# groovegrid_v2.net
KiCad netlist of a schematic drawn in EAGLE
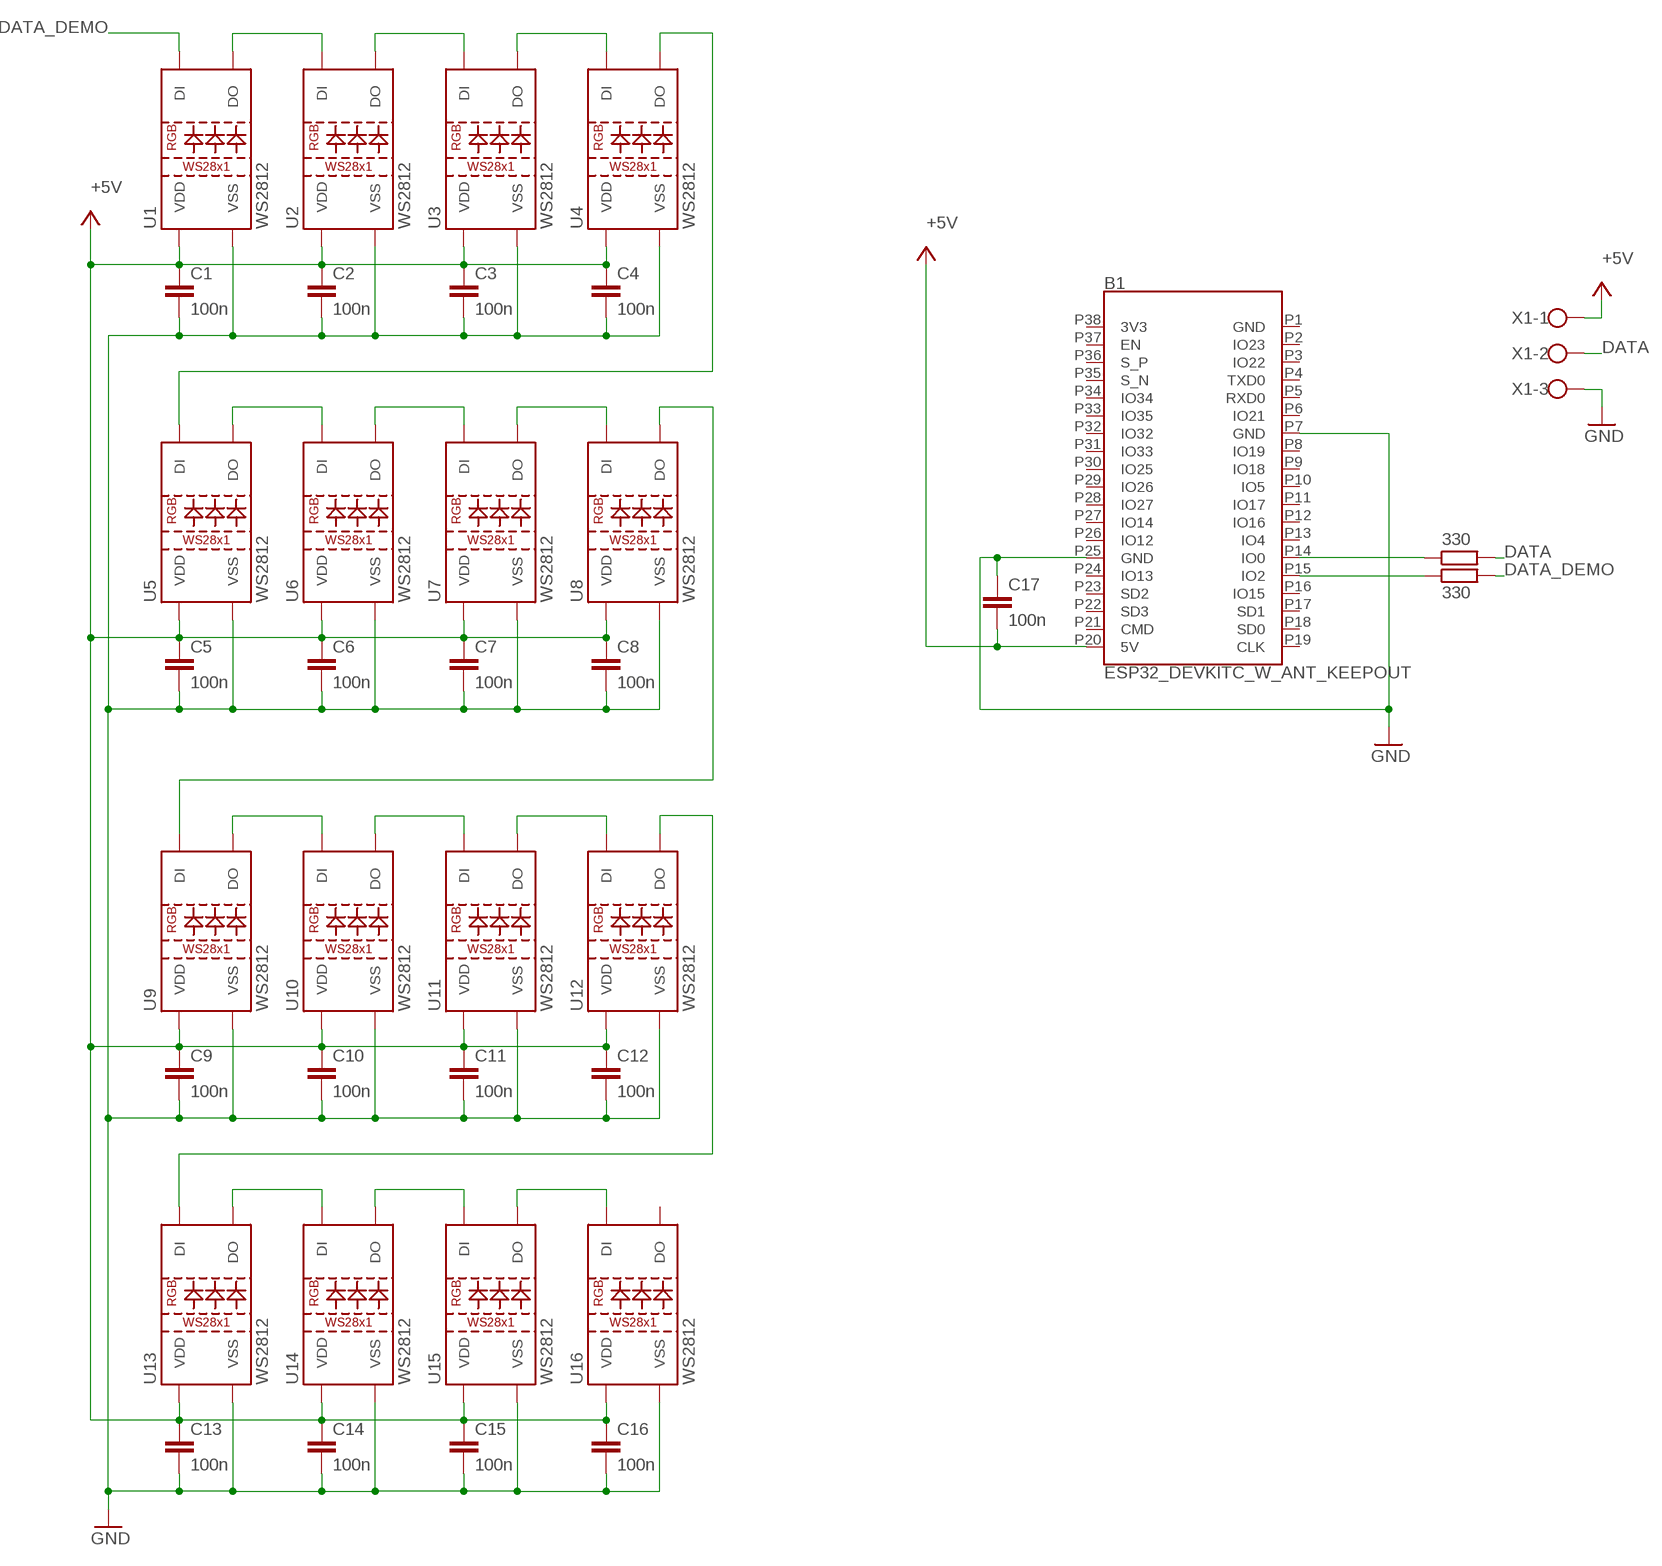
[diagram p0: schematic, sheet 1]

(export (version "E")
  (design (tool "Eeschema 10.0.6"))
  (components
    (comp (ref "B1")
      (value "ESP32_DEVKITC_W_ANT_KEEPOUT")
      (footprint "eagle-import:ESP32_DEVKITC")
      (libsource (lib "eagle-import") (part "ESP32_DEVKITC_W_ANT_KEEPOUT"))
    )
    (comp (ref "C1")
      (value "100n")
      (footprint "eagle-import:C0805")
      (libsource (lib "eagle-import") (part "C-EUC0805"))
    )
    (comp (ref "C2")
      (value "100n")
      (footprint "eagle-import:C0805")
      (libsource (lib "eagle-import") (part "C-EUC0805"))
    )
    (comp (ref "C3")
      (value "100n")
      (footprint "eagle-import:C0805")
      (libsource (lib "eagle-import") (part "C-EUC0805"))
    )
    (comp (ref "C4")
      (value "100n")
      (footprint "eagle-import:C0805")
      (libsource (lib "eagle-import") (part "C-EUC0805"))
    )
    (comp (ref "C5")
      (value "100n")
      (footprint "eagle-import:C0805")
      (libsource (lib "eagle-import") (part "C-EUC0805"))
    )
    (comp (ref "C6")
      (value "100n")
      (footprint "eagle-import:C0805")
      (libsource (lib "eagle-import") (part "C-EUC0805"))
    )
    (comp (ref "C7")
      (value "100n")
      (footprint "eagle-import:C0805")
      (libsource (lib "eagle-import") (part "C-EUC0805"))
    )
    (comp (ref "C8")
      (value "100n")
      (footprint "eagle-import:C0805")
      (libsource (lib "eagle-import") (part "C-EUC0805"))
    )
    (comp (ref "C9")
      (value "100n")
      (footprint "eagle-import:C0805")
      (libsource (lib "eagle-import") (part "C-EUC0805"))
    )
    (comp (ref "C10")
      (value "100n")
      (footprint "eagle-import:C0805")
      (libsource (lib "eagle-import") (part "C-EUC0805"))
    )
    (comp (ref "C11")
      (value "100n")
      (footprint "eagle-import:C0805")
      (libsource (lib "eagle-import") (part "C-EUC0805"))
    )
    (comp (ref "C12")
      (value "100n")
      (footprint "eagle-import:C0805")
      (libsource (lib "eagle-import") (part "C-EUC0805"))
    )
    (comp (ref "C13")
      (value "100n")
      (footprint "eagle-import:C0805")
      (libsource (lib "eagle-import") (part "C-EUC0805"))
    )
    (comp (ref "C14")
      (value "100n")
      (footprint "eagle-import:C0805")
      (libsource (lib "eagle-import") (part "C-EUC0805"))
    )
    (comp (ref "C15")
      (value "100n")
      (footprint "eagle-import:C0805")
      (libsource (lib "eagle-import") (part "C-EUC0805"))
    )
    (comp (ref "C16")
      (value "100n")
      (footprint "eagle-import:C0805")
      (libsource (lib "eagle-import") (part "C-EUC0805"))
    )
    (comp (ref "C17")
      (value "100n")
      (footprint "eagle-import:C0805")
      (libsource (lib "eagle-import") (part "C-EUC0805"))
    )
    (comp (ref "R1")
      (value "330")
      (footprint "eagle-import:R0805")
      (libsource (lib "eagle-import") (part "R-EU_R0805"))
    )
    (comp (ref "R2")
      (value "330")
      (footprint "eagle-import:R0805")
      (libsource (lib "eagle-import") (part "R-EU_R0805"))
    )
    (comp (ref "U1")
      (value "WS2812")
      (footprint "eagle-import:LED-TRICOLOR-5050-IC")
      (libsource (lib "eagle-import") (part "WS2812{dblquote}"))
    )
    (comp (ref "U2")
      (value "WS2812")
      (footprint "eagle-import:LED-TRICOLOR-5050-IC")
      (libsource (lib "eagle-import") (part "WS2812{dblquote}"))
    )
    (comp (ref "U3")
      (value "WS2812")
      (footprint "eagle-import:LED-TRICOLOR-5050-IC")
      (libsource (lib "eagle-import") (part "WS2812{dblquote}"))
    )
    (comp (ref "U4")
      (value "WS2812")
      (footprint "eagle-import:LED-TRICOLOR-5050-IC")
      (libsource (lib "eagle-import") (part "WS2812{dblquote}"))
    )
    (comp (ref "U5")
      (value "WS2812")
      (footprint "eagle-import:LED-TRICOLOR-5050-IC")
      (libsource (lib "eagle-import") (part "WS2812{dblquote}"))
    )
    (comp (ref "U6")
      (value "WS2812")
      (footprint "eagle-import:LED-TRICOLOR-5050-IC")
      (libsource (lib "eagle-import") (part "WS2812{dblquote}"))
    )
    (comp (ref "U7")
      (value "WS2812")
      (footprint "eagle-import:LED-TRICOLOR-5050-IC")
      (libsource (lib "eagle-import") (part "WS2812{dblquote}"))
    )
    (comp (ref "U8")
      (value "WS2812")
      (footprint "eagle-import:LED-TRICOLOR-5050-IC")
      (libsource (lib "eagle-import") (part "WS2812{dblquote}"))
    )
    (comp (ref "U9")
      (value "WS2812")
      (footprint "eagle-import:LED-TRICOLOR-5050-IC")
      (libsource (lib "eagle-import") (part "WS2812{dblquote}"))
    )
    (comp (ref "U10")
      (value "WS2812")
      (footprint "eagle-import:LED-TRICOLOR-5050-IC")
      (libsource (lib "eagle-import") (part "WS2812{dblquote}"))
    )
    (comp (ref "U11")
      (value "WS2812")
      (footprint "eagle-import:LED-TRICOLOR-5050-IC")
      (libsource (lib "eagle-import") (part "WS2812{dblquote}"))
    )
    (comp (ref "U12")
      (value "WS2812")
      (footprint "eagle-import:LED-TRICOLOR-5050-IC")
      (libsource (lib "eagle-import") (part "WS2812{dblquote}"))
    )
    (comp (ref "U13")
      (value "WS2812")
      (footprint "eagle-import:LED-TRICOLOR-5050-IC")
      (libsource (lib "eagle-import") (part "WS2812{dblquote}"))
    )
    (comp (ref "U14")
      (value "WS2812")
      (footprint "eagle-import:LED-TRICOLOR-5050-IC")
      (libsource (lib "eagle-import") (part "WS2812{dblquote}"))
    )
    (comp (ref "U15")
      (value "WS2812")
      (footprint "eagle-import:LED-TRICOLOR-5050-IC")
      (libsource (lib "eagle-import") (part "WS2812{dblquote}"))
    )
    (comp (ref "U16")
      (value "WS2812")
      (footprint "eagle-import:LED-TRICOLOR-5050-IC")
      (libsource (lib "eagle-import") (part "WS2812{dblquote}"))
    )
    (comp (ref "X1")
      (value "W237-103")
      (footprint "eagle-import:W237-103")
      (fields (field (name "MPN") "237-103"))
      (libsource (lib "eagle-import") (part "W237-103"))
    )
  )
  (nets
    (net (code "1") (name "+5V") (class "Default")
      (node (ref "B1") (pin "P20") (pinfunction "5V_P20") (pintype "bidirectional"))
      (node (ref "C1") (pin "1") (pinfunction "1_1") (pintype "passive"))
      (node (ref "C10") (pin "1") (pinfunction "1_1") (pintype "passive"))
      (node (ref "C11") (pin "1") (pinfunction "1_1") (pintype "passive"))
      (node (ref "C12") (pin "1") (pinfunction "1_1") (pintype "passive"))
      (node (ref "C13") (pin "1") (pinfunction "1_1") (pintype "passive"))
      (node (ref "C14") (pin "1") (pinfunction "1_1") (pintype "passive"))
      (node (ref "C15") (pin "1") (pinfunction "1_1") (pintype "passive"))
      (node (ref "C16") (pin "1") (pinfunction "1_1") (pintype "passive"))
      (node (ref "C17") (pin "2") (pinfunction "2_2") (pintype "passive"))
      (node (ref "C2") (pin "1") (pinfunction "1_1") (pintype "passive"))
      (node (ref "C3") (pin "1") (pinfunction "1_1") (pintype "passive"))
      (node (ref "C4") (pin "1") (pinfunction "1_1") (pintype "passive"))
      (node (ref "C5") (pin "1") (pinfunction "1_1") (pintype "passive"))
      (node (ref "C6") (pin "1") (pinfunction "1_1") (pintype "passive"))
      (node (ref "C7") (pin "1") (pinfunction "1_1") (pintype "passive"))
      (node (ref "C8") (pin "1") (pinfunction "1_1") (pintype "passive"))
      (node (ref "C9") (pin "1") (pinfunction "1_1") (pintype "passive"))
      (node (ref "U1") (pin "3") (pinfunction "VDD_3") (pintype "bidirectional"))
      (node (ref "U1") (pin "5") (pinfunction "VDD_5") (pintype "bidirectional"))
      (node (ref "U10") (pin "3") (pinfunction "VDD_3") (pintype "bidirectional"))
      (node (ref "U10") (pin "5") (pinfunction "VDD_5") (pintype "bidirectional"))
      (node (ref "U11") (pin "3") (pinfunction "VDD_3") (pintype "bidirectional"))
      (node (ref "U11") (pin "5") (pinfunction "VDD_5") (pintype "bidirectional"))
      (node (ref "U12") (pin "3") (pinfunction "VDD_3") (pintype "bidirectional"))
      (node (ref "U12") (pin "5") (pinfunction "VDD_5") (pintype "bidirectional"))
      (node (ref "U13") (pin "3") (pinfunction "VDD_3") (pintype "bidirectional"))
      (node (ref "U13") (pin "5") (pinfunction "VDD_5") (pintype "bidirectional"))
      (node (ref "U14") (pin "3") (pinfunction "VDD_3") (pintype "bidirectional"))
      (node (ref "U14") (pin "5") (pinfunction "VDD_5") (pintype "bidirectional"))
      (node (ref "U15") (pin "3") (pinfunction "VDD_3") (pintype "bidirectional"))
      (node (ref "U15") (pin "5") (pinfunction "VDD_5") (pintype "bidirectional"))
      (node (ref "U16") (pin "3") (pinfunction "VDD_3") (pintype "bidirectional"))
      (node (ref "U16") (pin "5") (pinfunction "VDD_5") (pintype "bidirectional"))
      (node (ref "U2") (pin "3") (pinfunction "VDD_3") (pintype "bidirectional"))
      (node (ref "U2") (pin "5") (pinfunction "VDD_5") (pintype "bidirectional"))
      (node (ref "U3") (pin "3") (pinfunction "VDD_3") (pintype "bidirectional"))
      (node (ref "U3") (pin "5") (pinfunction "VDD_5") (pintype "bidirectional"))
      (node (ref "U4") (pin "3") (pinfunction "VDD_3") (pintype "bidirectional"))
      (node (ref "U4") (pin "5") (pinfunction "VDD_5") (pintype "bidirectional"))
      (node (ref "U5") (pin "3") (pinfunction "VDD_3") (pintype "bidirectional"))
      (node (ref "U5") (pin "5") (pinfunction "VDD_5") (pintype "bidirectional"))
      (node (ref "U6") (pin "3") (pinfunction "VDD_3") (pintype "bidirectional"))
      (node (ref "U6") (pin "5") (pinfunction "VDD_5") (pintype "bidirectional"))
      (node (ref "U7") (pin "3") (pinfunction "VDD_3") (pintype "bidirectional"))
      (node (ref "U7") (pin "5") (pinfunction "VDD_5") (pintype "bidirectional"))
      (node (ref "U8") (pin "3") (pinfunction "VDD_3") (pintype "bidirectional"))
      (node (ref "U8") (pin "5") (pinfunction "VDD_5") (pintype "bidirectional"))
      (node (ref "U9") (pin "3") (pinfunction "VDD_3") (pintype "bidirectional"))
      (node (ref "U9") (pin "5") (pinfunction "VDD_5") (pintype "bidirectional"))
      (node (ref "X1") (pin "1") (pinfunction "KL_1") (pintype "passive"))
    )
    (net (code "2") (name "/DATA") (class "Default")
      (node (ref "R1") (pin "2") (pinfunction "2_2") (pintype "passive"))
      (node (ref "X1") (pin "2") (pinfunction "KL_2") (pintype "passive"))
    )
    (net (code "3") (name "/DATA_DEMO") (class "Default")
      (node (ref "R2") (pin "2") (pinfunction "2_2") (pintype "passive"))
      (node (ref "U1") (pin "2") (pinfunction "DI_2") (pintype "bidirectional"))
    )
    (net (code "4") (name "GND") (class "Default")
      (node (ref "B1") (pin "P25") (pinfunction "GND_P25") (pintype "bidirectional"))
      (node (ref "B1") (pin "P7") (pinfunction "GND_P7") (pintype "bidirectional"))
      (node (ref "C1") (pin "2") (pinfunction "2_2") (pintype "passive"))
      (node (ref "C10") (pin "2") (pinfunction "2_2") (pintype "passive"))
      (node (ref "C11") (pin "2") (pinfunction "2_2") (pintype "passive"))
      (node (ref "C12") (pin "2") (pinfunction "2_2") (pintype "passive"))
      (node (ref "C13") (pin "2") (pinfunction "2_2") (pintype "passive"))
      (node (ref "C14") (pin "2") (pinfunction "2_2") (pintype "passive"))
      (node (ref "C15") (pin "2") (pinfunction "2_2") (pintype "passive"))
      (node (ref "C16") (pin "2") (pinfunction "2_2") (pintype "passive"))
      (node (ref "C17") (pin "1") (pinfunction "1_1") (pintype "passive"))
      (node (ref "C2") (pin "2") (pinfunction "2_2") (pintype "passive"))
      (node (ref "C3") (pin "2") (pinfunction "2_2") (pintype "passive"))
      (node (ref "C4") (pin "2") (pinfunction "2_2") (pintype "passive"))
      (node (ref "C5") (pin "2") (pinfunction "2_2") (pintype "passive"))
      (node (ref "C6") (pin "2") (pinfunction "2_2") (pintype "passive"))
      (node (ref "C7") (pin "2") (pinfunction "2_2") (pintype "passive"))
      (node (ref "C8") (pin "2") (pinfunction "2_2") (pintype "passive"))
      (node (ref "C9") (pin "2") (pinfunction "2_2") (pintype "passive"))
      (node (ref "U1") (pin "6") (pinfunction "VSS_6") (pintype "bidirectional"))
      (node (ref "U10") (pin "6") (pinfunction "VSS_6") (pintype "bidirectional"))
      (node (ref "U11") (pin "6") (pinfunction "VSS_6") (pintype "bidirectional"))
      (node (ref "U12") (pin "6") (pinfunction "VSS_6") (pintype "bidirectional"))
      (node (ref "U13") (pin "6") (pinfunction "VSS_6") (pintype "bidirectional"))
      (node (ref "U14") (pin "6") (pinfunction "VSS_6") (pintype "bidirectional"))
      (node (ref "U15") (pin "6") (pinfunction "VSS_6") (pintype "bidirectional"))
      (node (ref "U16") (pin "6") (pinfunction "VSS_6") (pintype "bidirectional"))
      (node (ref "U2") (pin "6") (pinfunction "VSS_6") (pintype "bidirectional"))
      (node (ref "U3") (pin "6") (pinfunction "VSS_6") (pintype "bidirectional"))
      (node (ref "U4") (pin "6") (pinfunction "VSS_6") (pintype "bidirectional"))
      (node (ref "U5") (pin "6") (pinfunction "VSS_6") (pintype "bidirectional"))
      (node (ref "U6") (pin "6") (pinfunction "VSS_6") (pintype "bidirectional"))
      (node (ref "U7") (pin "6") (pinfunction "VSS_6") (pintype "bidirectional"))
      (node (ref "U8") (pin "6") (pinfunction "VSS_6") (pintype "bidirectional"))
      (node (ref "U9") (pin "6") (pinfunction "VSS_6") (pintype "bidirectional"))
      (node (ref "X1") (pin "3") (pinfunction "KL_3") (pintype "passive"))
    )
    (net (code "5") (name "Net-(B1-IO0)") (class "Default")
      (node (ref "B1") (pin "P14") (pinfunction "IO0_P14") (pintype "bidirectional"))
      (node (ref "R1") (pin "1") (pinfunction "1_1") (pintype "passive"))
    )
    (net (code "6") (name "Net-(B1-IO2)") (class "Default")
      (node (ref "B1") (pin "P15") (pinfunction "IO2_P15") (pintype "bidirectional"))
      (node (ref "R2") (pin "1") (pinfunction "1_1") (pintype "passive"))
    )
    (net (code "7") (name "Net-(U1-DO)") (class "Default")
      (node (ref "U1") (pin "1") (pinfunction "DO_1") (pintype "bidirectional"))
      (node (ref "U2") (pin "2") (pinfunction "DI_2") (pintype "bidirectional"))
    )
    (net (code "8") (name "Net-(U2-DO)") (class "Default")
      (node (ref "U2") (pin "1") (pinfunction "DO_1") (pintype "bidirectional"))
      (node (ref "U3") (pin "2") (pinfunction "DI_2") (pintype "bidirectional"))
    )
    (net (code "9") (name "Net-(U3-DO)") (class "Default")
      (node (ref "U3") (pin "1") (pinfunction "DO_1") (pintype "bidirectional"))
      (node (ref "U4") (pin "2") (pinfunction "DI_2") (pintype "bidirectional"))
    )
    (net (code "10") (name "Net-(U4-DO)") (class "Default")
      (node (ref "U4") (pin "1") (pinfunction "DO_1") (pintype "bidirectional"))
      (node (ref "U5") (pin "2") (pinfunction "DI_2") (pintype "bidirectional"))
    )
    (net (code "11") (name "Net-(U5-DO)") (class "Default")
      (node (ref "U5") (pin "1") (pinfunction "DO_1") (pintype "bidirectional"))
      (node (ref "U6") (pin "2") (pinfunction "DI_2") (pintype "bidirectional"))
    )
    (net (code "12") (name "Net-(U6-DO)") (class "Default")
      (node (ref "U6") (pin "1") (pinfunction "DO_1") (pintype "bidirectional"))
      (node (ref "U7") (pin "2") (pinfunction "DI_2") (pintype "bidirectional"))
    )
    (net (code "13") (name "Net-(U7-DO)") (class "Default")
      (node (ref "U7") (pin "1") (pinfunction "DO_1") (pintype "bidirectional"))
      (node (ref "U8") (pin "2") (pinfunction "DI_2") (pintype "bidirectional"))
    )
    (net (code "14") (name "Net-(U8-DO)") (class "Default")
      (node (ref "U8") (pin "1") (pinfunction "DO_1") (pintype "bidirectional"))
      (node (ref "U9") (pin "2") (pinfunction "DI_2") (pintype "bidirectional"))
    )
    (net (code "15") (name "Net-(U10-DI)") (class "Default")
      (node (ref "U10") (pin "2") (pinfunction "DI_2") (pintype "bidirectional"))
      (node (ref "U9") (pin "1") (pinfunction "DO_1") (pintype "bidirectional"))
    )
    (net (code "16") (name "Net-(U10-DO)") (class "Default")
      (node (ref "U10") (pin "1") (pinfunction "DO_1") (pintype "bidirectional"))
      (node (ref "U11") (pin "2") (pinfunction "DI_2") (pintype "bidirectional"))
    )
    (net (code "17") (name "Net-(U11-DO)") (class "Default")
      (node (ref "U11") (pin "1") (pinfunction "DO_1") (pintype "bidirectional"))
      (node (ref "U12") (pin "2") (pinfunction "DI_2") (pintype "bidirectional"))
    )
    (net (code "18") (name "Net-(U12-DO)") (class "Default")
      (node (ref "U12") (pin "1") (pinfunction "DO_1") (pintype "bidirectional"))
      (node (ref "U13") (pin "2") (pinfunction "DI_2") (pintype "bidirectional"))
    )
    (net (code "19") (name "Net-(U13-DO)") (class "Default")
      (node (ref "U13") (pin "1") (pinfunction "DO_1") (pintype "bidirectional"))
      (node (ref "U14") (pin "2") (pinfunction "DI_2") (pintype "bidirectional"))
    )
    (net (code "20") (name "Net-(U14-DO)") (class "Default")
      (node (ref "U14") (pin "1") (pinfunction "DO_1") (pintype "bidirectional"))
      (node (ref "U15") (pin "2") (pinfunction "DI_2") (pintype "bidirectional"))
    )
    (net (code "21") (name "Net-(U15-DO)") (class "Default")
      (node (ref "U15") (pin "1") (pinfunction "DO_1") (pintype "bidirectional"))
      (node (ref "U16") (pin "2") (pinfunction "DI_2") (pintype "bidirectional"))
    )
    (net (code "22") (name "unconnected-(B1-3V3-PadP38)") (class "Default")
      (node (ref "B1") (pin "P38") (pinfunction "3V3_P38") (pintype "bidirectional"))
    )
    (net (code "23") (name "unconnected-(B1-CLK-PadP19)") (class "Default")
      (node (ref "B1") (pin "P19") (pinfunction "CLK_P19") (pintype "bidirectional"))
    )
    (net (code "24") (name "unconnected-(B1-CMD-PadP21)") (class "Default")
      (node (ref "B1") (pin "P21") (pinfunction "CMD_P21") (pintype "bidirectional"))
    )
    (net (code "25") (name "unconnected-(B1-EN-PadP37)") (class "Default")
      (node (ref "B1") (pin "P37") (pinfunction "EN_P37") (pintype "bidirectional"))
    )
    (net (code "26") (name "unconnected-(B1-GND-PadP1)") (class "Default")
      (node (ref "B1") (pin "P1") (pinfunction "GND_P1") (pintype "bidirectional"))
    )
    (net (code "27") (name "unconnected-(B1-IO4-PadP13)") (class "Default")
      (node (ref "B1") (pin "P13") (pinfunction "IO4_P13") (pintype "bidirectional"))
    )
    (net (code "28") (name "unconnected-(B1-IO5-PadP10)") (class "Default")
      (node (ref "B1") (pin "P10") (pinfunction "IO5_P10") (pintype "bidirectional"))
    )
    (net (code "29") (name "unconnected-(B1-IO12-PadP26)") (class "Default")
      (node (ref "B1") (pin "P26") (pinfunction "IO12_P26") (pintype "bidirectional"))
    )
    (net (code "30") (name "unconnected-(B1-IO13-PadP24)") (class "Default")
      (node (ref "B1") (pin "P24") (pinfunction "IO13_P24") (pintype "bidirectional"))
    )
    (net (code "31") (name "unconnected-(B1-IO14-PadP27)") (class "Default")
      (node (ref "B1") (pin "P27") (pinfunction "IO14_P27") (pintype "bidirectional"))
    )
    (net (code "32") (name "unconnected-(B1-IO15-PadP16)") (class "Default")
      (node (ref "B1") (pin "P16") (pinfunction "IO15_P16") (pintype "bidirectional"))
    )
    (net (code "33") (name "unconnected-(B1-IO16-PadP12)") (class "Default")
      (node (ref "B1") (pin "P12") (pinfunction "IO16_P12") (pintype "bidirectional"))
    )
    (net (code "34") (name "unconnected-(B1-IO17-PadP11)") (class "Default")
      (node (ref "B1") (pin "P11") (pinfunction "IO17_P11") (pintype "bidirectional"))
    )
    (net (code "35") (name "unconnected-(B1-IO18-PadP9)") (class "Default")
      (node (ref "B1") (pin "P9") (pinfunction "IO18_P9") (pintype "bidirectional"))
    )
    (net (code "36") (name "unconnected-(B1-IO19-PadP8)") (class "Default")
      (node (ref "B1") (pin "P8") (pinfunction "IO19_P8") (pintype "bidirectional"))
    )
    (net (code "37") (name "unconnected-(B1-IO21-PadP6)") (class "Default")
      (node (ref "B1") (pin "P6") (pinfunction "IO21_P6") (pintype "bidirectional"))
    )
    (net (code "38") (name "unconnected-(B1-IO22-PadP3)") (class "Default")
      (node (ref "B1") (pin "P3") (pinfunction "IO22_P3") (pintype "bidirectional"))
    )
    (net (code "39") (name "unconnected-(B1-IO23-PadP2)") (class "Default")
      (node (ref "B1") (pin "P2") (pinfunction "IO23_P2") (pintype "bidirectional"))
    )
    (net (code "40") (name "unconnected-(B1-IO25-PadP30)") (class "Default")
      (node (ref "B1") (pin "P30") (pinfunction "IO25_P30") (pintype "bidirectional"))
    )
    (net (code "41") (name "unconnected-(B1-IO26-PadP29)") (class "Default")
      (node (ref "B1") (pin "P29") (pinfunction "IO26_P29") (pintype "bidirectional"))
    )
    (net (code "42") (name "unconnected-(B1-IO27-PadP28)") (class "Default")
      (node (ref "B1") (pin "P28") (pinfunction "IO27_P28") (pintype "bidirectional"))
    )
    (net (code "43") (name "unconnected-(B1-IO32-PadP32)") (class "Default")
      (node (ref "B1") (pin "P32") (pinfunction "IO32_P32") (pintype "bidirectional"))
    )
    (net (code "44") (name "unconnected-(B1-IO33-PadP31)") (class "Default")
      (node (ref "B1") (pin "P31") (pinfunction "IO33_P31") (pintype "bidirectional"))
    )
    (net (code "45") (name "unconnected-(B1-IO34-PadP34)") (class "Default")
      (node (ref "B1") (pin "P34") (pinfunction "IO34_P34") (pintype "bidirectional"))
    )
    (net (code "46") (name "unconnected-(B1-IO35-PadP33)") (class "Default")
      (node (ref "B1") (pin "P33") (pinfunction "IO35_P33") (pintype "bidirectional"))
    )
    (net (code "47") (name "unconnected-(B1-RXD0-PadP5)") (class "Default")
      (node (ref "B1") (pin "P5") (pinfunction "RXD0_P5") (pintype "bidirectional"))
    )
    (net (code "48") (name "unconnected-(B1-SD0-PadP18)") (class "Default")
      (node (ref "B1") (pin "P18") (pinfunction "SD0_P18") (pintype "bidirectional"))
    )
    (net (code "49") (name "unconnected-(B1-SD1-PadP17)") (class "Default")
      (node (ref "B1") (pin "P17") (pinfunction "SD1_P17") (pintype "bidirectional"))
    )
    (net (code "50") (name "unconnected-(B1-SD2-PadP23)") (class "Default")
      (node (ref "B1") (pin "P23") (pinfunction "SD2_P23") (pintype "bidirectional"))
    )
    (net (code "51") (name "unconnected-(B1-SD3-PadP22)") (class "Default")
      (node (ref "B1") (pin "P22") (pinfunction "SD3_P22") (pintype "bidirectional"))
    )
    (net (code "52") (name "unconnected-(B1-S_N-PadP35)") (class "Default")
      (node (ref "B1") (pin "P35") (pinfunction "S_N_P35") (pintype "bidirectional"))
    )
    (net (code "53") (name "unconnected-(B1-S_P-PadP36)") (class "Default")
      (node (ref "B1") (pin "P36") (pinfunction "S_P_P36") (pintype "bidirectional"))
    )
    (net (code "54") (name "unconnected-(B1-TXD0-PadP4)") (class "Default")
      (node (ref "B1") (pin "P4") (pinfunction "TXD0_P4") (pintype "bidirectional"))
    )
    (net (code "55") (name "unconnected-(U16-DO-Pad1)") (class "Default")
      (node (ref "U16") (pin "1") (pinfunction "DO_1") (pintype "bidirectional"))
    )
  )
)
